# Timer_555.net
KiCad netlist of a schematic drawn in Altium Designer
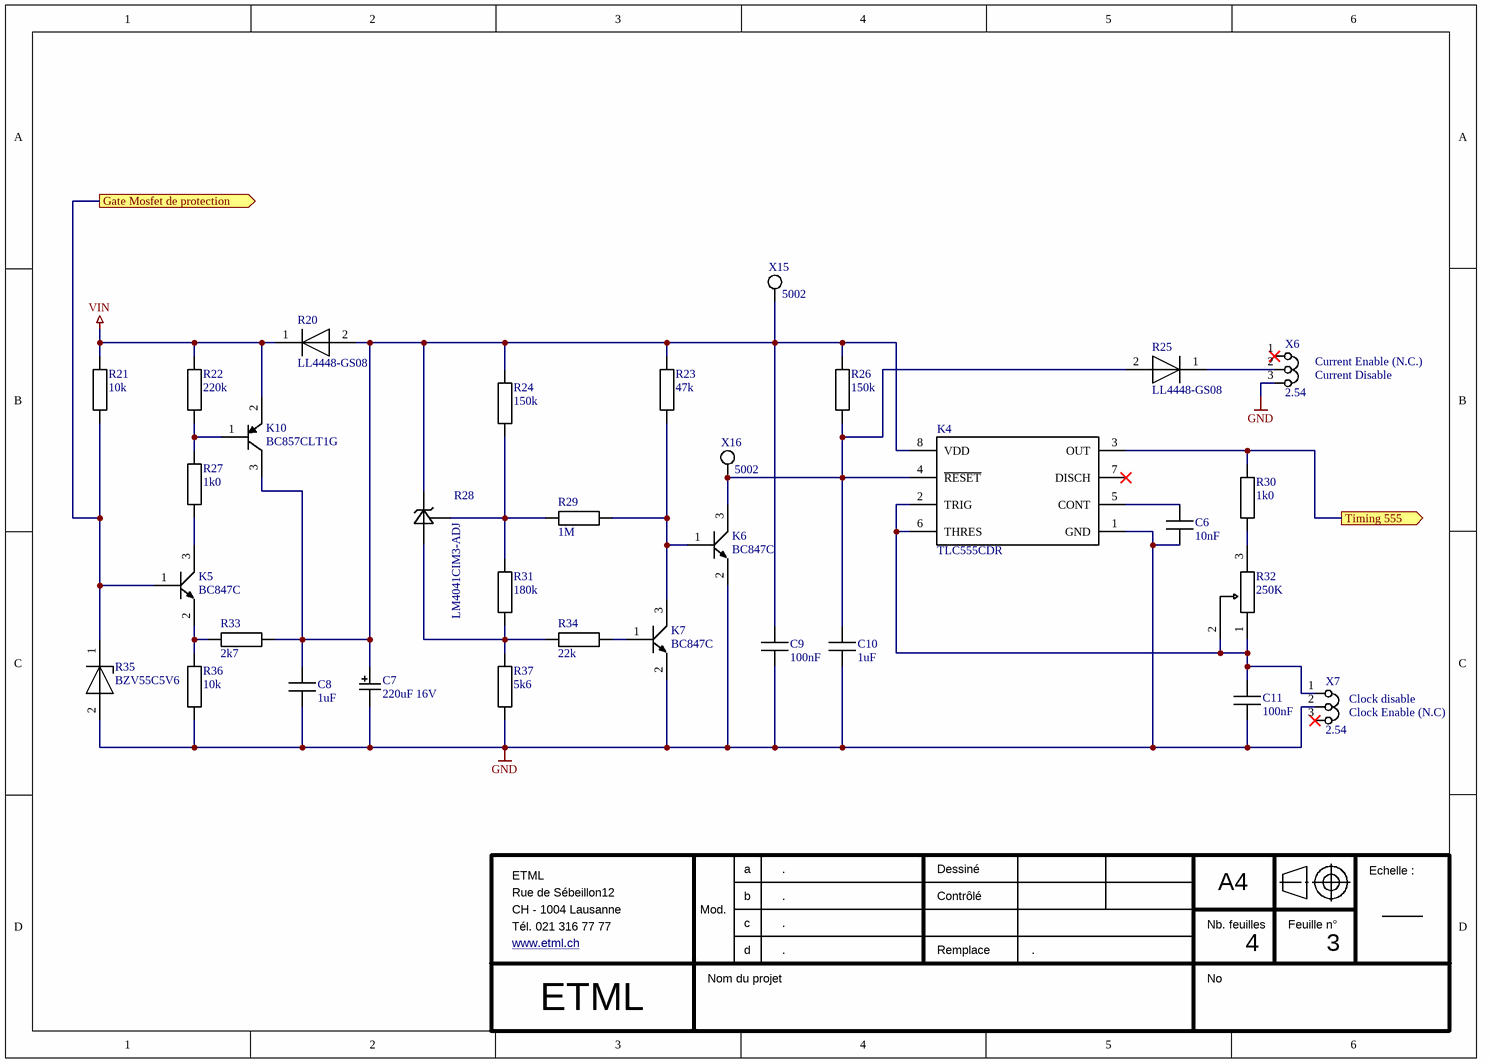
[diagram p0: Timer 555.SchDoc]

(export (version "E")
  (design (tool "Eeschema 10.0.6"))
  (components
    (comp (ref "C6")
      (value "10nF")
      (footprint "CAPC1608X08M")
      (description "CAPC 10nF X7R 50V 10% 1608 (0603 INCH)")
      (fields (field (name "MANUFACTURER") "TDK") (field (name "VOLTAGE") "50V"))
      (libsource (lib "ETML-ES") (part "CAP"))
    )
    (comp (ref "C7")
      (value "220uF 16V")
      (footprint "NIC-CAPA2-6.3X7.7_V")
      (description "Aluminum Electrolytic Capacitor,  220 uF, 16 V, + / - 20%,  6.3 x 7.7 mm D x L")
      (fields (field (name "PARTNUMBER") "UUD1C221MCL1GS") (field (name "MANUFACTURER") "Nichicon"))
      (libsource (lib "220uF 16V") (part "CMP-0687-00060-1"))
    )
    (comp (ref "C8")
      (value "1uF")
      (footprint "CAPC2012X08M")
      (description "CAPC 1uF X5R 25V 10% 2012 (0805 INCH)")
      (fields (field (name "MANUFACTURER") "TDK") (field (name "TOLERANCE") "±10%"))
      (libsource (lib "ETML-ES") (part "CAP"))
    )
    (comp (ref "C9")
      (value "100nF")
      (footprint "CAPC2012X08M")
      (description "CAPC 100nF X7R 50V 10% 2012 (0805 INCH)")
      (fields (field (name "VOLTAGE") "50V") (field (name "MANUFACTURER") "TDK"))
      (libsource (lib "ETML-ES") (part "CAP"))
    )
    (comp (ref "C10")
      (value "1uF")
      (footprint "CAPC2012X08M")
      (description "CAPC 1uF X5R 25V 10% 2012 (0805 INCH)")
      (fields (field (name "MANUFACTURER") "TDK") (field (name "TOLERANCE") "±10%"))
      (libsource (lib "ETML-ES") (part "CAP"))
    )
    (comp (ref "C11")
      (value "100nF")
      (footprint "CAPC2012X08M")
      (description "CAPC 100nF X7R 50V 10% 2012 (0805 INCH)")
      (fields (field (name "VOLTAGE") "50V") (field (name "MANUFACTURER") "TDK"))
      (libsource (lib "ETML-ES") (part "CAP"))
    )
    (comp (ref "K4")
      (value "TLC555CDR")
      (footprint "FP-D0008A-IPC_B")
      (description "IC OSC SGL TIMER 2.1MHZ 8-SOIC")
      (libsource (lib "TLC555CD") (part "CMP-04857-000001-1"))
    )
    (comp (ref "K5")
      (value "BC847C")
      (footprint "SOT90P240X110-3M")
      (description "NPN general purpose transistor")
      (libsource (lib "BC847C") (part "BC847C"))
    )
    (comp (ref "K6")
      (value "BC847C")
      (footprint "SOT90P240X110-3M")
      (description "NPN general purpose transistor")
      (libsource (lib "BC847C") (part "BC847C"))
    )
    (comp (ref "K7")
      (value "BC847C")
      (footprint "SOT90P240X110-3M")
      (description "NPN general purpose transistor")
      (libsource (lib "BC847C") (part "BC847C"))
    )
    (comp (ref "K10")
      (value "BC857CLT1G")
      (footprint "ONSC-SOT-23-3-318-08_V")
      (description "General Purpose Transistor, PNP Silicon, 3-Pin SOT-23, Pb-Free, Tape and Reel, BC857CLT1G")
      (fields (field (name "MANUFACTURER") "On Semiconductor"))
      (libsource (lib "BC857") (part "CMP-1048-00802-1"))
    )
    (comp (ref "R20")
      (value "LL4448-GS08")
      (footprint "FP-6_560-5005_01-4-MFG")
      (description "DIODE GEN PURP 75V 150MA SOD80")
      (fields
        (field (name "MANUFACTURER") "Vishay Small Signal")
        (field (name "OCTOPART") "https://octopart.com/ll4448-gs08-vishay+small+signal-40886")
      )
      (libsource (lib "LL4448") (part "CMP-249167-000001-1"))
    )
    (comp (ref "R21")
      (value "10k")
      (footprint "RESC2012X06M")
      (description "RES 10kohm  ±1% 0.125W 2012 (0805 INCH)")
      (fields (field (name "TOLERANCE") "±1%") (field (name "VOLTAGE") "150V"))
      (libsource (lib "ETML-ES") (part "RES"))
    )
    (comp (ref "R22")
      (value "220k")
      (footprint "RESC2012X06M")
      (description "RES 220kohm  ±1% 0.125W 2012 (0805 INCH)")
      (fields (field (name "POWER") "0.125W") (field (name "TOLERANCE") "±1%"))
      (libsource (lib "ETML-ES") (part "RES"))
    )
    (comp (ref "R23")
      (value "47k")
      (footprint "RESC2012X06M")
      (description "RES 47kohm  ±1% 0.125W 2012 (0805 INCH)")
      (fields (field (name "MANUFACTURER") "Yageo") (field (name "VOLTAGE") "150V"))
      (libsource (lib "ETML-ES") (part "RES"))
    )
    (comp (ref "R24")
      (value "150k")
      (footprint "RESC2012X06M")
      (description "RES 150kohm  ±1% 0.125W 2012 (0805 INCH)")
      (fields (field (name "TOLERANCE") "±1%") (field (name "VOLTAGE") "150V"))
      (libsource (lib "ETML-ES") (part "RES"))
    )
    (comp (ref "R25")
      (value "LL4448-GS08")
      (footprint "FP-6_560-5005_01-4-MFG")
      (description "DIODE GEN PURP 75V 150MA SOD80")
      (fields
        (field (name "MANUFACTURER") "Vishay Small Signal")
        (field (name "OCTOPART") "https://octopart.com/ll4448-gs08-vishay+small+signal-40886")
      )
      (libsource (lib "LL4448") (part "CMP-249167-000001-1"))
    )
    (comp (ref "R26")
      (value "150k")
      (footprint "RESC2012X06M")
      (description "RES 150kohm  ±1% 0.125W 2012 (0805 INCH)")
      (fields (field (name "TOLERANCE") "±1%") (field (name "VOLTAGE") "150V"))
      (libsource (lib "ETML-ES") (part "RES"))
    )
    (comp (ref "R27")
      (value "1k0")
      (footprint "RESC2012X06M")
      (description "RES 1.0kohm  ±1% 0.125W 2012 (0805 INCH)")
      (fields (field (name "MANUFACTURER") "Yageo") (field (name "TOLERANCE") "±1%"))
      (libsource (lib "ETML-ES") (part "RES"))
    )
    (comp (ref "R28")
      (value "LM4041CIM3-ADJ")
      (footprint "DBZ0003A_M")
      (description "Precision Micropower Shunt Voltage Reference, 3-pin SOT-23")
      (fields (field (name "MANUFACTURER") "Texas Instruments"))
      (libsource (lib "LM4041") (part "CMP-0074-00726-3"))
    )
    (comp (ref "R29")
      (value "1M")
      (footprint "RESC2012X06M")
      (description "RES 1.0Mohm  ±1% 0.125W 2012 (0805 INCH)")
      (fields (field (name "MANUFACTURER") "Yageo") (field (name "VOLTAGE") "150V"))
      (libsource (lib "ETML-ES") (part "RES"))
    )
    (comp (ref "R30")
      (value "1k0")
      (footprint "RESC2012X06M")
      (description "RES 1.0kohm  ±1% 0.125W 2012 (0805 INCH)")
      (fields (field (name "MANUFACTURER") "Yageo") (field (name "TOLERANCE") "±1%"))
      (libsource (lib "ETML-ES") (part "RES"))
    )
    (comp (ref "R31")
      (value "180k")
      (footprint "RESC2012X06M")
      (description "RES 180kohm  ±1% 0.125W 2012 (0805 INCH)")
      (fields (field (name "MANUFACTURER") "Yageo") (field (name "POWER") "0.125W"))
      (libsource (lib "ETML-ES") (part "RES"))
    )
    (comp (ref "R32")
      (value "250K")
      (footprint "FP-3296W-MFG")
      (description "TRIMMER 250K OHM 0.5W PC PIN TOP")
      (fields
        (field (name "OCTOPART") "https://octopart.com/3296w-1-254lf-bourns-574856")
        (field (name "MANUFACTURER") "Bourns")
      )
      (libsource (lib "Pot250K") (part "CMP-07234-000001-1"))
    )
    (comp (ref "R33")
      (value "2k7")
      (footprint "RESC2012X06M")
      (description "RES 2.7kohm  ±1% 0.125W 2012 (0805 INCH)")
      (fields (field (name "POWER") "0.125W") (field (name "MANUFACTURER") "Yageo"))
      (libsource (lib "ETML-ES") (part "RES"))
    )
    (comp (ref "R34")
      (value "22k")
      (footprint "RESC2012X06M")
      (description "RES 22kohm  ±1% 0.125W 2012 (0805 INCH)")
      (fields (field (name "TOLERANCE") "±1%") (field (name "MANUFACTURER") "Yageo"))
      (libsource (lib "ETML-ES") (part "RES"))
    )
    (comp (ref "R35")
      (value "BZV55C5V6")
      (footprint "FP-DO-213AA-MFG")
      (description "BZV55C5V6 Diode Zener Single 5.6V 2% 3.33mW 2-Pin MELF DO-213AA Bag")
      (fields (field (name "TOLERANCE") "7%"))
      (libsource (lib "BZV55-C5V6") (part "CMP-00252-16640727-1"))
    )
    (comp (ref "R36")
      (value "10k")
      (footprint "RESC2012X06M")
      (description "RES 10kohm  ±1% 0.125W 2012 (0805 INCH)")
      (fields (field (name "TOLERANCE") "±1%") (field (name "VOLTAGE") "150V"))
      (libsource (lib "ETML-ES") (part "RES"))
    )
    (comp (ref "R37")
      (value "5k6")
      (footprint "RESC2012X06M")
      (description "RES 5.6kohm  ±1% 0.125W 2012 (0805 INCH)")
      (fields (field (name "POWER") "0.125W") (field (name "MANUFACTURER") "Yageo"))
      (libsource (lib "ETML-ES") (part "RES"))
    )
    (comp (ref "X6")
      (value "2.54")
      (footprint "PIN-1x03-2.54")
      (description "JUMPER 2.54 1x03")
      (fields (field (name "MANUFACTURER") "Würth Electronik") (field (name "VOLTAGE") "250VAC"))
      (libsource (lib "ETML-ES") (part "JUMP-1x3"))
    )
    (comp (ref "X7")
      (value "2.54")
      (footprint "PIN-1x03-2.54")
      (description "JUMPER 2.54 1x03")
      (fields (field (name "MANUFACTURER") "Würth Electronik") (field (name "VOLTAGE") "250VAC"))
      (libsource (lib "ETML-ES") (part "JUMP-1x3"))
    )
    (comp (ref "X15")
      (value "5002")
      (footprint "Keystone_5002")
      (description "TEST THT MINIATURE WT")
      (fields (field (name "MANUFACTURER") "Keystone"))
      (libsource (lib "ETML-ES") (part "TEST"))
    )
    (comp (ref "X16")
      (value "5002")
      (footprint "Keystone_5002")
      (description "TEST THT MINIATURE WT")
      (fields (field (name "MANUFACTURER") "Keystone"))
      (libsource (lib "ETML-ES") (part "TEST"))
    )
  )
  (nets
    (net (code "1") (name "/Gate Mosfet de protection") (class "Default")
      (node (ref "K5") (pin "1") (pinfunction "Base_1") (pintype "passive"))
      (node (ref "R21") (pin "1") (pinfunction "1_1") (pintype "passive"))
      (node (ref "R35") (pin "1") (pinfunction "C_1") (pintype "passive"))
    )
    (net (code "2") (name "/Timing 555") (class "Default")
      (node (ref "K4") (pin "3") (pinfunction "OUT_3") (pintype "passive"))
      (node (ref "R30") (pin "2") (pinfunction "2_2") (pintype "passive"))
    )
    (net (code "3") (name "GND") (class "Default")
      (node (ref "C10") (pin "1") (pinfunction "1_1") (pintype "passive"))
      (node (ref "C11") (pin "1") (pinfunction "1_1") (pintype "passive"))
      (node (ref "C6") (pin "1") (pinfunction "1_1") (pintype "passive"))
      (node (ref "C7") (pin "2") (pinfunction "2_2") (pintype "passive"))
      (node (ref "C8") (pin "1") (pinfunction "1_1") (pintype "passive"))
      (node (ref "C9") (pin "1") (pinfunction "1_1") (pintype "passive"))
      (node (ref "K4") (pin "1") (pinfunction "GND_1") (pintype "power_in"))
      (node (ref "K6") (pin "2") (pinfunction "Collector_2") (pintype "passive"))
      (node (ref "K7") (pin "2") (pinfunction "Collector_2") (pintype "passive"))
      (node (ref "R35") (pin "2") (pinfunction "A_2") (pintype "passive"))
      (node (ref "R36") (pin "1") (pinfunction "1_1") (pintype "passive"))
      (node (ref "R37") (pin "1") (pinfunction "1_1") (pintype "passive"))
      (node (ref "X6") (pin "3") (pinfunction "3_3") (pintype "passive"))
      (node (ref "X7") (pin "2") (pinfunction "2_2") (pintype "passive"))
    )
    (net (code "4") (name "Net-(K4-CONT)") (class "Default")
      (node (ref "C6") (pin "2") (pinfunction "2_2") (pintype "passive"))
      (node (ref "K4") (pin "5") (pinfunction "CONT_5") (pintype "power_in"))
    )
    (net (code "5") (name "Net-(K4-THRES)") (class "Default")
      (node (ref "C11") (pin "2") (pinfunction "2_2") (pintype "passive"))
      (node (ref "K4") (pin "2") (pinfunction "TRIG_2") (pintype "power_in"))
      (node (ref "K4") (pin "6") (pinfunction "THRES_6") (pintype "power_in"))
      (node (ref "R32") (pin "1") (pinfunction "CCW_1") (pintype "passive"))
      (node (ref "R32") (pin "2") (pinfunction "WIPER_2") (pintype "passive"))
      (node (ref "X7") (pin "1") (pinfunction "0_1") (pintype "passive"))
    )
    (net (code "6") (name "Net-(K4-~{RESET})") (class "Default")
      (node (ref "C10") (pin "2") (pinfunction "2_2") (pintype "passive"))
      (node (ref "K4") (pin "4") (pinfunction "~{RESET}_4") (pintype "power_in"))
      (node (ref "K6") (pin "3") (pinfunction "Emitter_3") (pintype "passive"))
      (node (ref "R25") (pin "2") (pinfunction "A_2") (pintype "passive"))
      (node (ref "R26") (pin "1") (pinfunction "1_1") (pintype "passive"))
      (node (ref "X16") (pin "1") (pinfunction "TP_1") (pintype "passive"))
    )
    (net (code "7") (name "Net-(K5-Collector)") (class "Default")
      (node (ref "K5") (pin "2") (pinfunction "Collector_2") (pintype "passive"))
      (node (ref "R33") (pin "1") (pinfunction "1_1") (pintype "passive"))
      (node (ref "R36") (pin "2") (pinfunction "2_2") (pintype "passive"))
    )
    (net (code "8") (name "Net-(K5-Emitter)") (class "Default")
      (node (ref "K5") (pin "3") (pinfunction "Emitter_3") (pintype "passive"))
      (node (ref "R27") (pin "1") (pinfunction "1_1") (pintype "passive"))
    )
    (net (code "9") (name "Net-(K6-Base)") (class "Default")
      (node (ref "K6") (pin "1") (pinfunction "Base_1") (pintype "passive"))
      (node (ref "K7") (pin "3") (pinfunction "Emitter_3") (pintype "passive"))
      (node (ref "R23") (pin "1") (pinfunction "1_1") (pintype "passive"))
      (node (ref "R29") (pin "1") (pinfunction "1_1") (pintype "passive"))
    )
    (net (code "10") (name "Net-(K7-Base)") (class "Default")
      (node (ref "K7") (pin "1") (pinfunction "Base_1") (pintype "passive"))
      (node (ref "R34") (pin "2") (pinfunction "2_2") (pintype "passive"))
    )
    (net (code "11") (name "Net-(K10-B)") (class "Default")
      (node (ref "K10") (pin "1") (pinfunction "B_1") (pintype "passive"))
      (node (ref "R22") (pin "1") (pinfunction "1_1") (pintype "passive"))
      (node (ref "R27") (pin "2") (pinfunction "2_2") (pintype "passive"))
    )
    (net (code "12") (name "Net-(K10-C)") (class "Default")
      (node (ref "C7") (pin "1") (pinfunction "1_1") (pintype "passive"))
      (node (ref "C8") (pin "2") (pinfunction "2_2") (pintype "passive"))
      (node (ref "C9") (pin "2") (pinfunction "2_2") (pintype "passive"))
      (node (ref "K10") (pin "3") (pinfunction "C_3") (pintype "passive"))
      (node (ref "K4") (pin "8") (pinfunction "VDD_8") (pintype "power_in"))
      (node (ref "R20") (pin "2") (pinfunction "A_2") (pintype "passive"))
      (node (ref "R23") (pin "2") (pinfunction "2_2") (pintype "passive"))
      (node (ref "R24") (pin "2") (pinfunction "2_2") (pintype "passive"))
      (node (ref "R26") (pin "2") (pinfunction "2_2") (pintype "passive"))
      (node (ref "R28") (pin "2") (pinfunction "+V_2") (pintype "passive"))
      (node (ref "R33") (pin "2") (pinfunction "2_2") (pintype "passive"))
      (node (ref "X15") (pin "1") (pinfunction "TP_1") (pintype "passive"))
    )
    (net (code "13") (name "Net-(R25-C)") (class "Default")
      (node (ref "R25") (pin "1") (pinfunction "C_1") (pintype "passive"))
      (node (ref "X6") (pin "2") (pinfunction "2_2") (pintype "passive"))
    )
    (net (code "14") (name "Net-(R28--V)") (class "Default")
      (node (ref "R28") (pin "3") (pinfunction "-V_3") (pintype "passive"))
      (node (ref "R31") (pin "1") (pinfunction "1_1") (pintype "passive"))
      (node (ref "R34") (pin "1") (pinfunction "1_1") (pintype "passive"))
      (node (ref "R37") (pin "2") (pinfunction "2_2") (pintype "passive"))
    )
    (net (code "15") (name "Net-(R28-FB)") (class "Default")
      (node (ref "R24") (pin "1") (pinfunction "1_1") (pintype "passive"))
      (node (ref "R28") (pin "1") (pinfunction "FB_1") (pintype "power_in"))
      (node (ref "R29") (pin "2") (pinfunction "2_2") (pintype "passive"))
      (node (ref "R31") (pin "2") (pinfunction "2_2") (pintype "passive"))
    )
    (net (code "16") (name "Net-(R32-CW)") (class "Default")
      (node (ref "R30") (pin "1") (pinfunction "1_1") (pintype "passive"))
      (node (ref "R32") (pin "3") (pinfunction "CW_3") (pintype "passive"))
    )
    (net (code "17") (name "VIN") (class "Default")
      (node (ref "K10") (pin "2") (pinfunction "E_2") (pintype "passive"))
      (node (ref "R20") (pin "1") (pinfunction "C_1") (pintype "passive"))
      (node (ref "R21") (pin "2") (pinfunction "2_2") (pintype "passive"))
      (node (ref "R22") (pin "2") (pinfunction "2_2") (pintype "passive"))
    )
    (net (code "18") (name "unconnected-(K4-DISCH-Pad7)") (class "Default")
      (node (ref "K4") (pin "7") (pinfunction "DISCH_7") (pintype "power_in+no_connect"))
    )
    (net (code "19") (name "unconnected-(X6-0-Pad1)") (class "Default")
      (node (ref "X6") (pin "1") (pinfunction "0_1") (pintype "passive+no_connect"))
    )
    (net (code "20") (name "unconnected-(X7-Pad3)") (class "Default")
      (node (ref "X7") (pin "3") (pinfunction "3_3") (pintype "passive+no_connect"))
    )
  )
)
